# rotenc.net
KiCad netlist of a schematic drawn in Altium Designer
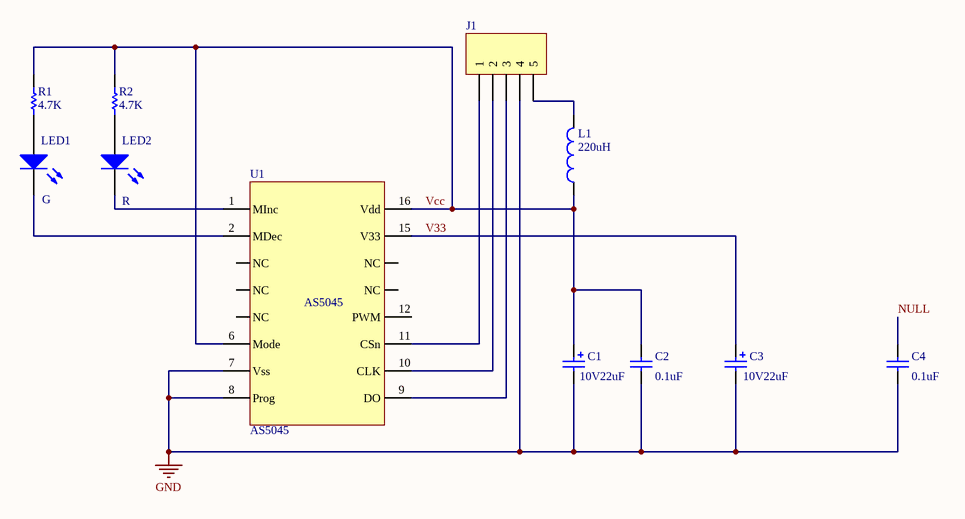
[diagram p0: rotenc.SchDoc]

(export (version "E")
  (design (tool "Eeschema 10.0.6"))
  (components
    (comp (ref "C1")
      (value "10V22uF")
      (footprint "CAP1210P")
      (description "Polarized Capacitor (Axial)")
      (fields (field (name "PUBLISHER") "Altium Limited"))
      (libsource (lib "magcontrol") (part "Cap Pol2"))
    )
    (comp (ref "C2")
      (value "0.1uF")
      (footprint "CAP0805")
      (description "Capacitor")
      (fields (field (name "PUBLISHER") "Altium Limited"))
      (libsource (lib "magcontrol") (part "Cap"))
    )
    (comp (ref "C3")
      (value "10V22uF")
      (footprint "CAP1210P")
      (description "Polarized Capacitor (Axial)")
      (fields (field (name "PUBLISHER") "Altium Limited"))
      (libsource (lib "magcontrol") (part "Cap Pol2"))
    )
    (comp (ref "C4")
      (value "0.1uF")
      (footprint "CAP1210")
      (description "Capacitor")
      (fields (field (name "PUBLISHER") "Altium Limited"))
      (libsource (lib "magcontrol") (part "Cap"))
    )
    (comp (ref "J1")
      (value "Header 5")
      (footprint "J5")
      (description "Header, 5-Pin")
      (fields (field (name "PUBLISHER") "Altium Limited"))
      (libsource (lib "Miscellaneous Connectors") (part "Header 5"))
    )
    (comp (ref "L1")
      (value "220uH")
      (footprint "IND1210")
      (description "Inductor")
      (fields (field (name "PUBLISHER") "Altium Limited"))
      (libsource (lib "magcontrol") (part "Inductor"))
    )
    (comp (ref "LED1")
      (value "G")
      (footprint "LED2G")
      (description "LED")
      (fields (field (name "PUBLISHER") "Altium Limited"))
      (libsource (lib "magcontrol") (part "LED"))
    )
    (comp (ref "LED2")
      (value "R")
      (footprint "LED2R")
      (description "LED")
      (fields (field (name "PUBLISHER") "Altium Limited"))
      (libsource (lib "magcontrol") (part "LED"))
    )
    (comp (ref "R1")
      (value "4.7K")
      (footprint "RES0805")
      (description "Resistor")
      (fields (field (name "PUBLISHER") "Altium Limited"))
      (libsource (lib "magcontrol") (part "Res1"))
    )
    (comp (ref "R2")
      (value "4.7K")
      (footprint "RES0805")
      (description "Resistor")
      (fields (field (name "PUBLISHER") "Altium Limited"))
      (libsource (lib "magcontrol") (part "Res1"))
    )
    (comp (ref "U1")
      (value "AS5045")
      (footprint "SSOP16")
      (description "Magnetic Rotary Encoder")
      (libsource (lib "magcontrol") (part "AS5045"))
    )
  )
  (nets
    (net (code "1") (name "/NULL") (class "Default")
      (node (ref "C4") (pin "2") (pinfunction "2_2") (pintype "passive"))
    )
    (net (code "2") (name "/V33") (class "Default")
      (node (ref "C3") (pin "1") (pinfunction "1_1") (pintype "passive"))
      (node (ref "U1") (pin "15") (pinfunction "V33_15") (pintype "passive"))
    )
    (net (code "3") (name "/Vcc") (class "Default")
      (node (ref "C1") (pin "1") (pinfunction "1_1") (pintype "passive"))
      (node (ref "C2") (pin "2") (pinfunction "2_2") (pintype "passive"))
      (node (ref "L1") (pin "1") (pinfunction "1_1") (pintype "passive"))
      (node (ref "R1") (pin "1") (pinfunction "1_1") (pintype "passive"))
      (node (ref "R2") (pin "1") (pinfunction "1_1") (pintype "passive"))
      (node (ref "U1") (pin "16") (pinfunction "Vdd_16") (pintype "passive"))
      (node (ref "U1") (pin "6") (pinfunction "Mode_6") (pintype "passive"))
    )
    (net (code "4") (name "GND") (class "Default")
      (node (ref "C1") (pin "2") (pinfunction "2_2") (pintype "passive"))
      (node (ref "C2") (pin "1") (pinfunction "1_1") (pintype "passive"))
      (node (ref "C3") (pin "2") (pinfunction "2_2") (pintype "passive"))
      (node (ref "C4") (pin "1") (pinfunction "1_1") (pintype "passive"))
      (node (ref "J1") (pin "4") (pinfunction "4_4") (pintype "passive"))
      (node (ref "U1") (pin "7") (pinfunction "Vss_7") (pintype "passive"))
      (node (ref "U1") (pin "8") (pinfunction "Prog_8") (pintype "passive"))
    )
    (net (code "5") (name "Net-(J1-Pad5)") (class "Default")
      (node (ref "J1") (pin "5") (pinfunction "5_5") (pintype "passive"))
      (node (ref "L1") (pin "2") (pinfunction "2_2") (pintype "passive"))
    )
    (net (code "6") (name "Net-(LED1-A)") (class "Default")
      (node (ref "LED1") (pin "1") (pinfunction "A_1") (pintype "passive"))
      (node (ref "R1") (pin "2") (pinfunction "2_2") (pintype "passive"))
    )
    (net (code "7") (name "Net-(LED1-K)") (class "Default")
      (node (ref "LED1") (pin "2") (pinfunction "K_2") (pintype "passive"))
      (node (ref "U1") (pin "2") (pinfunction "MDec_2") (pintype "passive"))
    )
    (net (code "8") (name "Net-(LED2-A)") (class "Default")
      (node (ref "LED2") (pin "1") (pinfunction "A_1") (pintype "passive"))
      (node (ref "R2") (pin "2") (pinfunction "2_2") (pintype "passive"))
    )
    (net (code "9") (name "Net-(LED2-K)") (class "Default")
      (node (ref "LED2") (pin "2") (pinfunction "K_2") (pintype "passive"))
      (node (ref "U1") (pin "1") (pinfunction "MInc_1") (pintype "passive"))
    )
    (net (code "10") (name "Net-(U1-CLK)") (class "Default")
      (node (ref "J1") (pin "2") (pinfunction "2_2") (pintype "passive"))
      (node (ref "U1") (pin "10") (pinfunction "CLK_10") (pintype "passive"))
    )
    (net (code "11") (name "Net-(U1-CSn)") (class "Default")
      (node (ref "J1") (pin "1") (pinfunction "1_1") (pintype "passive"))
      (node (ref "U1") (pin "11") (pinfunction "CSn_11") (pintype "passive"))
    )
    (net (code "12") (name "Net-(U1-DO)") (class "Default")
      (node (ref "J1") (pin "3") (pinfunction "3_3") (pintype "passive"))
      (node (ref "U1") (pin "9") (pinfunction "DO_9") (pintype "passive"))
    )
    (net (code "13") (name "unconnected-(U1-NC-Pad3)") (class "Default")
      (node (ref "U1") (pin "3") (pinfunction "NC_3") (pintype "power_in"))
    )
    (net (code "14") (name "unconnected-(U1-NC-Pad4)") (class "Default")
      (node (ref "U1") (pin "4") (pinfunction "NC_4") (pintype "passive"))
    )
    (net (code "15") (name "unconnected-(U1-NC-Pad5)") (class "Default")
      (node (ref "U1") (pin "5") (pinfunction "NC_5") (pintype "passive"))
    )
    (net (code "16") (name "unconnected-(U1-NC-Pad13)") (class "Default")
      (node (ref "U1") (pin "13") (pinfunction "NC_13") (pintype "passive"))
    )
    (net (code "17") (name "unconnected-(U1-NC-Pad14)") (class "Default")
      (node (ref "U1") (pin "14") (pinfunction "NC_14") (pintype "passive"))
    )
    (net (code "18") (name "unconnected-(U1-PWM-Pad12)") (class "Default")
      (node (ref "U1") (pin "12") (pinfunction "PWM_12") (pintype "passive"))
    )
  )
)
